# Controller_PCB_LED.net
KiCad netlist of a schematic drawn in Altium Designer
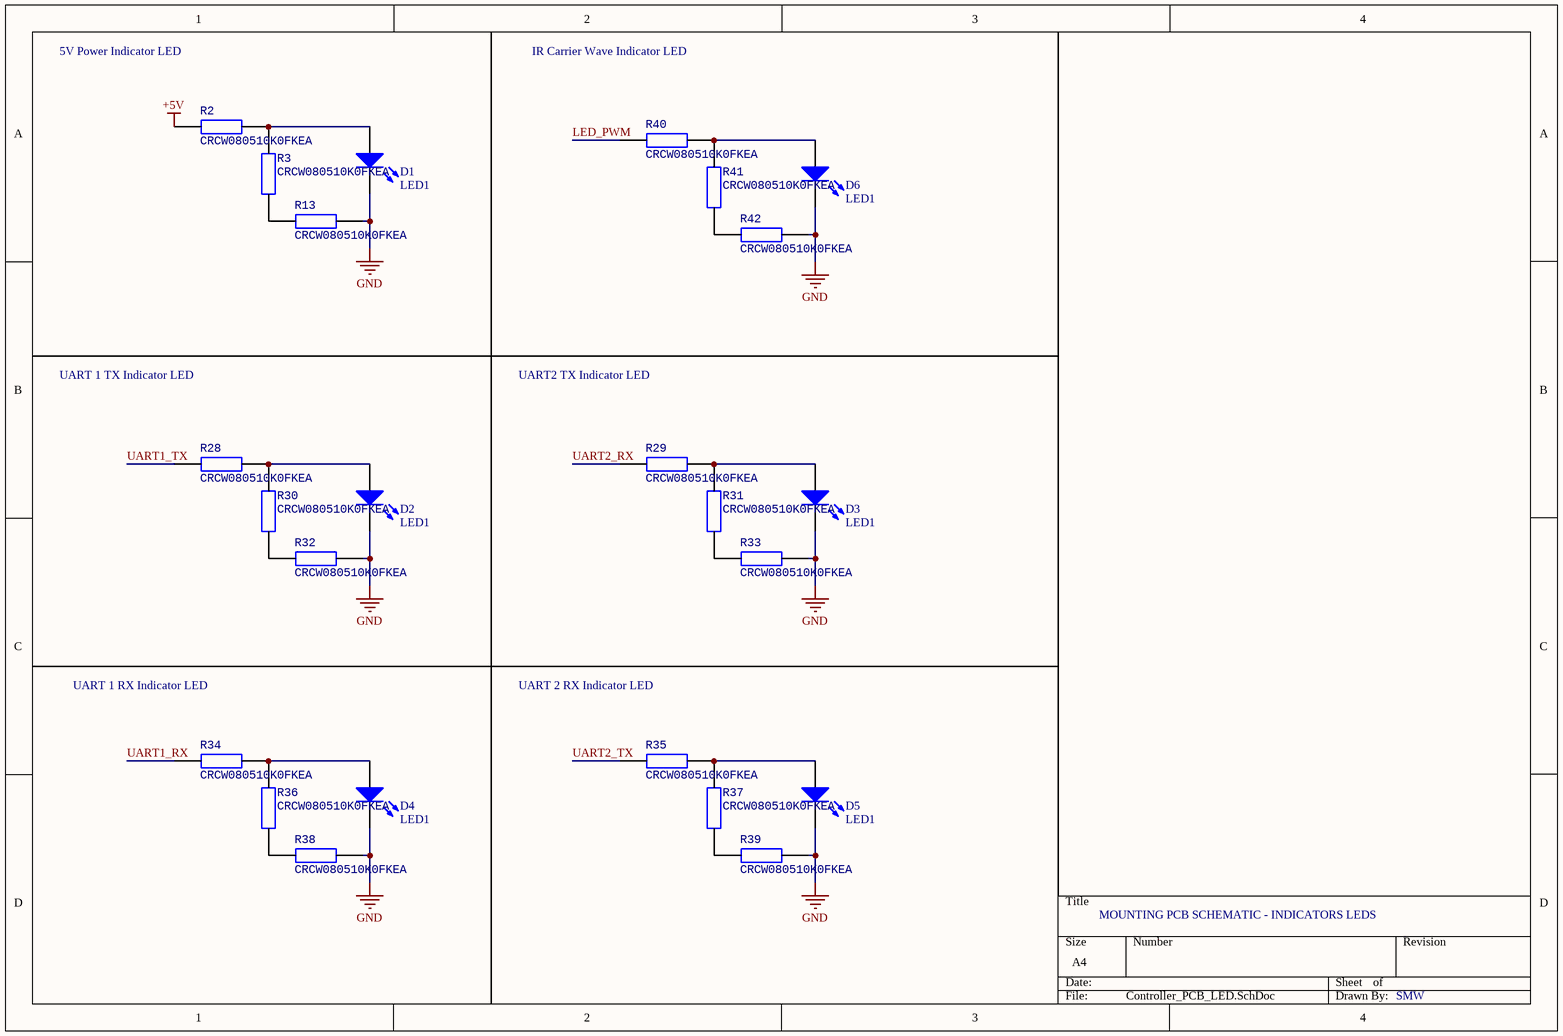
[diagram p0: Controller_PCB_LED.SchDoc]

(export (version "E")
  (design (tool "Eeschema 10.0.6"))
  (components
    (comp (ref "D1")
      (value "LED1")
      (footprint "L0603")
      (description "Typical RED GaAs LED")
      (fields (field (name "PUBLISHER") "Altium Limited"))
      (libsource (lib "Miscellaneous Devices") (part "LED1"))
    )
    (comp (ref "D2")
      (value "LED1")
      (footprint "L0603")
      (description "Typical RED GaAs LED")
      (fields (field (name "PUBLISHER") "Altium Limited"))
      (libsource (lib "Miscellaneous Devices") (part "LED1"))
    )
    (comp (ref "D3")
      (value "LED1")
      (footprint "L0603")
      (description "Typical RED GaAs LED")
      (fields (field (name "PUBLISHER") "Altium Limited"))
      (libsource (lib "Miscellaneous Devices") (part "LED1"))
    )
    (comp (ref "D4")
      (value "LED1")
      (footprint "L0603")
      (description "Typical RED GaAs LED")
      (fields (field (name "PUBLISHER") "Altium Limited"))
      (libsource (lib "Miscellaneous Devices") (part "LED1"))
    )
    (comp (ref "D5")
      (value "LED1")
      (footprint "L0603")
      (description "Typical RED GaAs LED")
      (fields (field (name "PUBLISHER") "Altium Limited"))
      (libsource (lib "Miscellaneous Devices") (part "LED1"))
    )
    (comp (ref "D6")
      (value "LED1")
      (footprint "L0603")
      (description "Typical RED GaAs LED")
      (fields (field (name "PUBLISHER") "Altium Limited"))
      (libsource (lib "Miscellaneous Devices") (part "LED1"))
    )
    (comp (ref "R2")
      (value "CRCW080510K0FKEA")
      (footprint "RESC2012X50N")
      (fields (field (name "RS PART NUMBER") "1694499"))
      (libsource (lib "CRCW080510K0FKEA") (part "CRCW080510K0FKEA"))
    )
    (comp (ref "R3")
      (value "CRCW080510K0FKEA")
      (footprint "RESC2012X50N")
      (fields (field (name "RS PART NUMBER") "1694499"))
      (libsource (lib "CRCW080510K0FKEA") (part "CRCW080510K0FKEA"))
    )
    (comp (ref "R13")
      (value "CRCW080510K0FKEA")
      (footprint "RESC2012X50N")
      (fields (field (name "RS PART NUMBER") "1694499"))
      (libsource (lib "CRCW080510K0FKEA") (part "CRCW080510K0FKEA"))
    )
    (comp (ref "R28")
      (value "CRCW080510K0FKEA")
      (footprint "RESC2012X50N")
      (fields (field (name "RS PART NUMBER") "1694499"))
      (libsource (lib "CRCW080510K0FKEA") (part "CRCW080510K0FKEA"))
    )
    (comp (ref "R29")
      (value "CRCW080510K0FKEA")
      (footprint "RESC2012X50N")
      (fields (field (name "RS PART NUMBER") "1694499"))
      (libsource (lib "CRCW080510K0FKEA") (part "CRCW080510K0FKEA"))
    )
    (comp (ref "R30")
      (value "CRCW080510K0FKEA")
      (footprint "RESC2012X50N")
      (fields (field (name "RS PART NUMBER") "1694499"))
      (libsource (lib "CRCW080510K0FKEA") (part "CRCW080510K0FKEA"))
    )
    (comp (ref "R31")
      (value "CRCW080510K0FKEA")
      (footprint "RESC2012X50N")
      (fields (field (name "RS PART NUMBER") "1694499"))
      (libsource (lib "CRCW080510K0FKEA") (part "CRCW080510K0FKEA"))
    )
    (comp (ref "R32")
      (value "CRCW080510K0FKEA")
      (footprint "RESC2012X50N")
      (fields (field (name "RS PART NUMBER") "1694499"))
      (libsource (lib "CRCW080510K0FKEA") (part "CRCW080510K0FKEA"))
    )
    (comp (ref "R33")
      (value "CRCW080510K0FKEA")
      (footprint "RESC2012X50N")
      (fields (field (name "RS PART NUMBER") "1694499"))
      (libsource (lib "CRCW080510K0FKEA") (part "CRCW080510K0FKEA"))
    )
    (comp (ref "R34")
      (value "CRCW080510K0FKEA")
      (footprint "RESC2012X50N")
      (fields (field (name "RS PART NUMBER") "1694499"))
      (libsource (lib "CRCW080510K0FKEA") (part "CRCW080510K0FKEA"))
    )
    (comp (ref "R35")
      (value "CRCW080510K0FKEA")
      (footprint "RESC2012X50N")
      (fields (field (name "RS PART NUMBER") "1694499"))
      (libsource (lib "CRCW080510K0FKEA") (part "CRCW080510K0FKEA"))
    )
    (comp (ref "R36")
      (value "CRCW080510K0FKEA")
      (footprint "RESC2012X50N")
      (fields (field (name "RS PART NUMBER") "1694499"))
      (libsource (lib "CRCW080510K0FKEA") (part "CRCW080510K0FKEA"))
    )
    (comp (ref "R37")
      (value "CRCW080510K0FKEA")
      (footprint "RESC2012X50N")
      (fields (field (name "RS PART NUMBER") "1694499"))
      (libsource (lib "CRCW080510K0FKEA") (part "CRCW080510K0FKEA"))
    )
    (comp (ref "R38")
      (value "CRCW080510K0FKEA")
      (footprint "RESC2012X50N")
      (fields (field (name "RS PART NUMBER") "1694499"))
      (libsource (lib "CRCW080510K0FKEA") (part "CRCW080510K0FKEA"))
    )
    (comp (ref "R39")
      (value "CRCW080510K0FKEA")
      (footprint "RESC2012X50N")
      (fields (field (name "RS PART NUMBER") "1694499"))
      (libsource (lib "CRCW080510K0FKEA") (part "CRCW080510K0FKEA"))
    )
    (comp (ref "R40")
      (value "CRCW080510K0FKEA")
      (footprint "RESC2012X50N")
      (fields (field (name "RS PART NUMBER") "1694499"))
      (libsource (lib "CRCW080510K0FKEA") (part "CRCW080510K0FKEA"))
    )
    (comp (ref "R41")
      (value "CRCW080510K0FKEA")
      (footprint "RESC2012X50N")
      (fields (field (name "RS PART NUMBER") "1694499"))
      (libsource (lib "CRCW080510K0FKEA") (part "CRCW080510K0FKEA"))
    )
    (comp (ref "R42")
      (value "CRCW080510K0FKEA")
      (footprint "RESC2012X50N")
      (fields (field (name "RS PART NUMBER") "1694499"))
      (libsource (lib "CRCW080510K0FKEA") (part "CRCW080510K0FKEA"))
    )
  )
  (nets
    (net (code "1") (name "+5V") (class "Default")
      (node (ref "R2") (pin "1") (pinfunction "1_1") (pintype "passive"))
    )
    (net (code "2") (name "/LED_PWM") (class "Default")
      (node (ref "R40") (pin "1") (pinfunction "1_1") (pintype "passive"))
    )
    (net (code "3") (name "/UART1_RX") (class "Default")
      (node (ref "R34") (pin "1") (pinfunction "1_1") (pintype "passive"))
    )
    (net (code "4") (name "/UART1_TX") (class "Default")
      (node (ref "R28") (pin "1") (pinfunction "1_1") (pintype "passive"))
    )
    (net (code "5") (name "/UART2_RX") (class "Default")
      (node (ref "R29") (pin "1") (pinfunction "1_1") (pintype "passive"))
    )
    (net (code "6") (name "/UART2_TX") (class "Default")
      (node (ref "R35") (pin "1") (pinfunction "1_1") (pintype "passive"))
    )
    (net (code "7") (name "GND") (class "Default")
      (node (ref "D1") (pin "2") (pinfunction "K_2") (pintype "passive"))
      (node (ref "D2") (pin "2") (pinfunction "K_2") (pintype "passive"))
      (node (ref "D3") (pin "2") (pinfunction "K_2") (pintype "passive"))
      (node (ref "D4") (pin "2") (pinfunction "K_2") (pintype "passive"))
      (node (ref "D5") (pin "2") (pinfunction "K_2") (pintype "passive"))
      (node (ref "D6") (pin "2") (pinfunction "K_2") (pintype "passive"))
      (node (ref "R13") (pin "1") (pinfunction "1_1") (pintype "passive"))
      (node (ref "R32") (pin "1") (pinfunction "1_1") (pintype "passive"))
      (node (ref "R33") (pin "1") (pinfunction "1_1") (pintype "passive"))
      (node (ref "R38") (pin "1") (pinfunction "1_1") (pintype "passive"))
      (node (ref "R39") (pin "1") (pinfunction "1_1") (pintype "passive"))
      (node (ref "R42") (pin "1") (pinfunction "1_1") (pintype "passive"))
    )
    (net (code "8") (name "Net-(D1-A)") (class "Default")
      (node (ref "D1") (pin "1") (pinfunction "A_1") (pintype "passive"))
      (node (ref "R2") (pin "2") (pinfunction "2_2") (pintype "passive"))
      (node (ref "R3") (pin "2") (pinfunction "2_2") (pintype "passive"))
    )
    (net (code "9") (name "Net-(D2-A)") (class "Default")
      (node (ref "D2") (pin "1") (pinfunction "A_1") (pintype "passive"))
      (node (ref "R28") (pin "2") (pinfunction "2_2") (pintype "passive"))
      (node (ref "R30") (pin "2") (pinfunction "2_2") (pintype "passive"))
    )
    (net (code "10") (name "Net-(D3-A)") (class "Default")
      (node (ref "D3") (pin "1") (pinfunction "A_1") (pintype "passive"))
      (node (ref "R29") (pin "2") (pinfunction "2_2") (pintype "passive"))
      (node (ref "R31") (pin "2") (pinfunction "2_2") (pintype "passive"))
    )
    (net (code "11") (name "Net-(D4-A)") (class "Default")
      (node (ref "D4") (pin "1") (pinfunction "A_1") (pintype "passive"))
      (node (ref "R34") (pin "2") (pinfunction "2_2") (pintype "passive"))
      (node (ref "R36") (pin "2") (pinfunction "2_2") (pintype "passive"))
    )
    (net (code "12") (name "Net-(D5-A)") (class "Default")
      (node (ref "D5") (pin "1") (pinfunction "A_1") (pintype "passive"))
      (node (ref "R35") (pin "2") (pinfunction "2_2") (pintype "passive"))
      (node (ref "R37") (pin "2") (pinfunction "2_2") (pintype "passive"))
    )
    (net (code "13") (name "Net-(D6-A)") (class "Default")
      (node (ref "D6") (pin "1") (pinfunction "A_1") (pintype "passive"))
      (node (ref "R40") (pin "2") (pinfunction "2_2") (pintype "passive"))
      (node (ref "R41") (pin "2") (pinfunction "2_2") (pintype "passive"))
    )
    (net (code "14") (name "Net-(R13-Pad2)") (class "Default")
      (node (ref "R13") (pin "2") (pinfunction "2_2") (pintype "passive"))
      (node (ref "R3") (pin "1") (pinfunction "1_1") (pintype "passive"))
    )
    (net (code "15") (name "Net-(R30-Pad1)") (class "Default")
      (node (ref "R30") (pin "1") (pinfunction "1_1") (pintype "passive"))
      (node (ref "R32") (pin "2") (pinfunction "2_2") (pintype "passive"))
    )
    (net (code "16") (name "Net-(R31-Pad1)") (class "Default")
      (node (ref "R31") (pin "1") (pinfunction "1_1") (pintype "passive"))
      (node (ref "R33") (pin "2") (pinfunction "2_2") (pintype "passive"))
    )
    (net (code "17") (name "Net-(R36-Pad1)") (class "Default")
      (node (ref "R36") (pin "1") (pinfunction "1_1") (pintype "passive"))
      (node (ref "R38") (pin "2") (pinfunction "2_2") (pintype "passive"))
    )
    (net (code "18") (name "Net-(R37-Pad1)") (class "Default")
      (node (ref "R37") (pin "1") (pinfunction "1_1") (pintype "passive"))
      (node (ref "R39") (pin "2") (pinfunction "2_2") (pintype "passive"))
    )
    (net (code "19") (name "Net-(R41-Pad1)") (class "Default")
      (node (ref "R41") (pin "1") (pinfunction "1_1") (pintype "passive"))
      (node (ref "R42") (pin "2") (pinfunction "2_2") (pintype "passive"))
    )
  )
)
